# Interface.net
KiCad netlist of a schematic drawn in Altium Designer
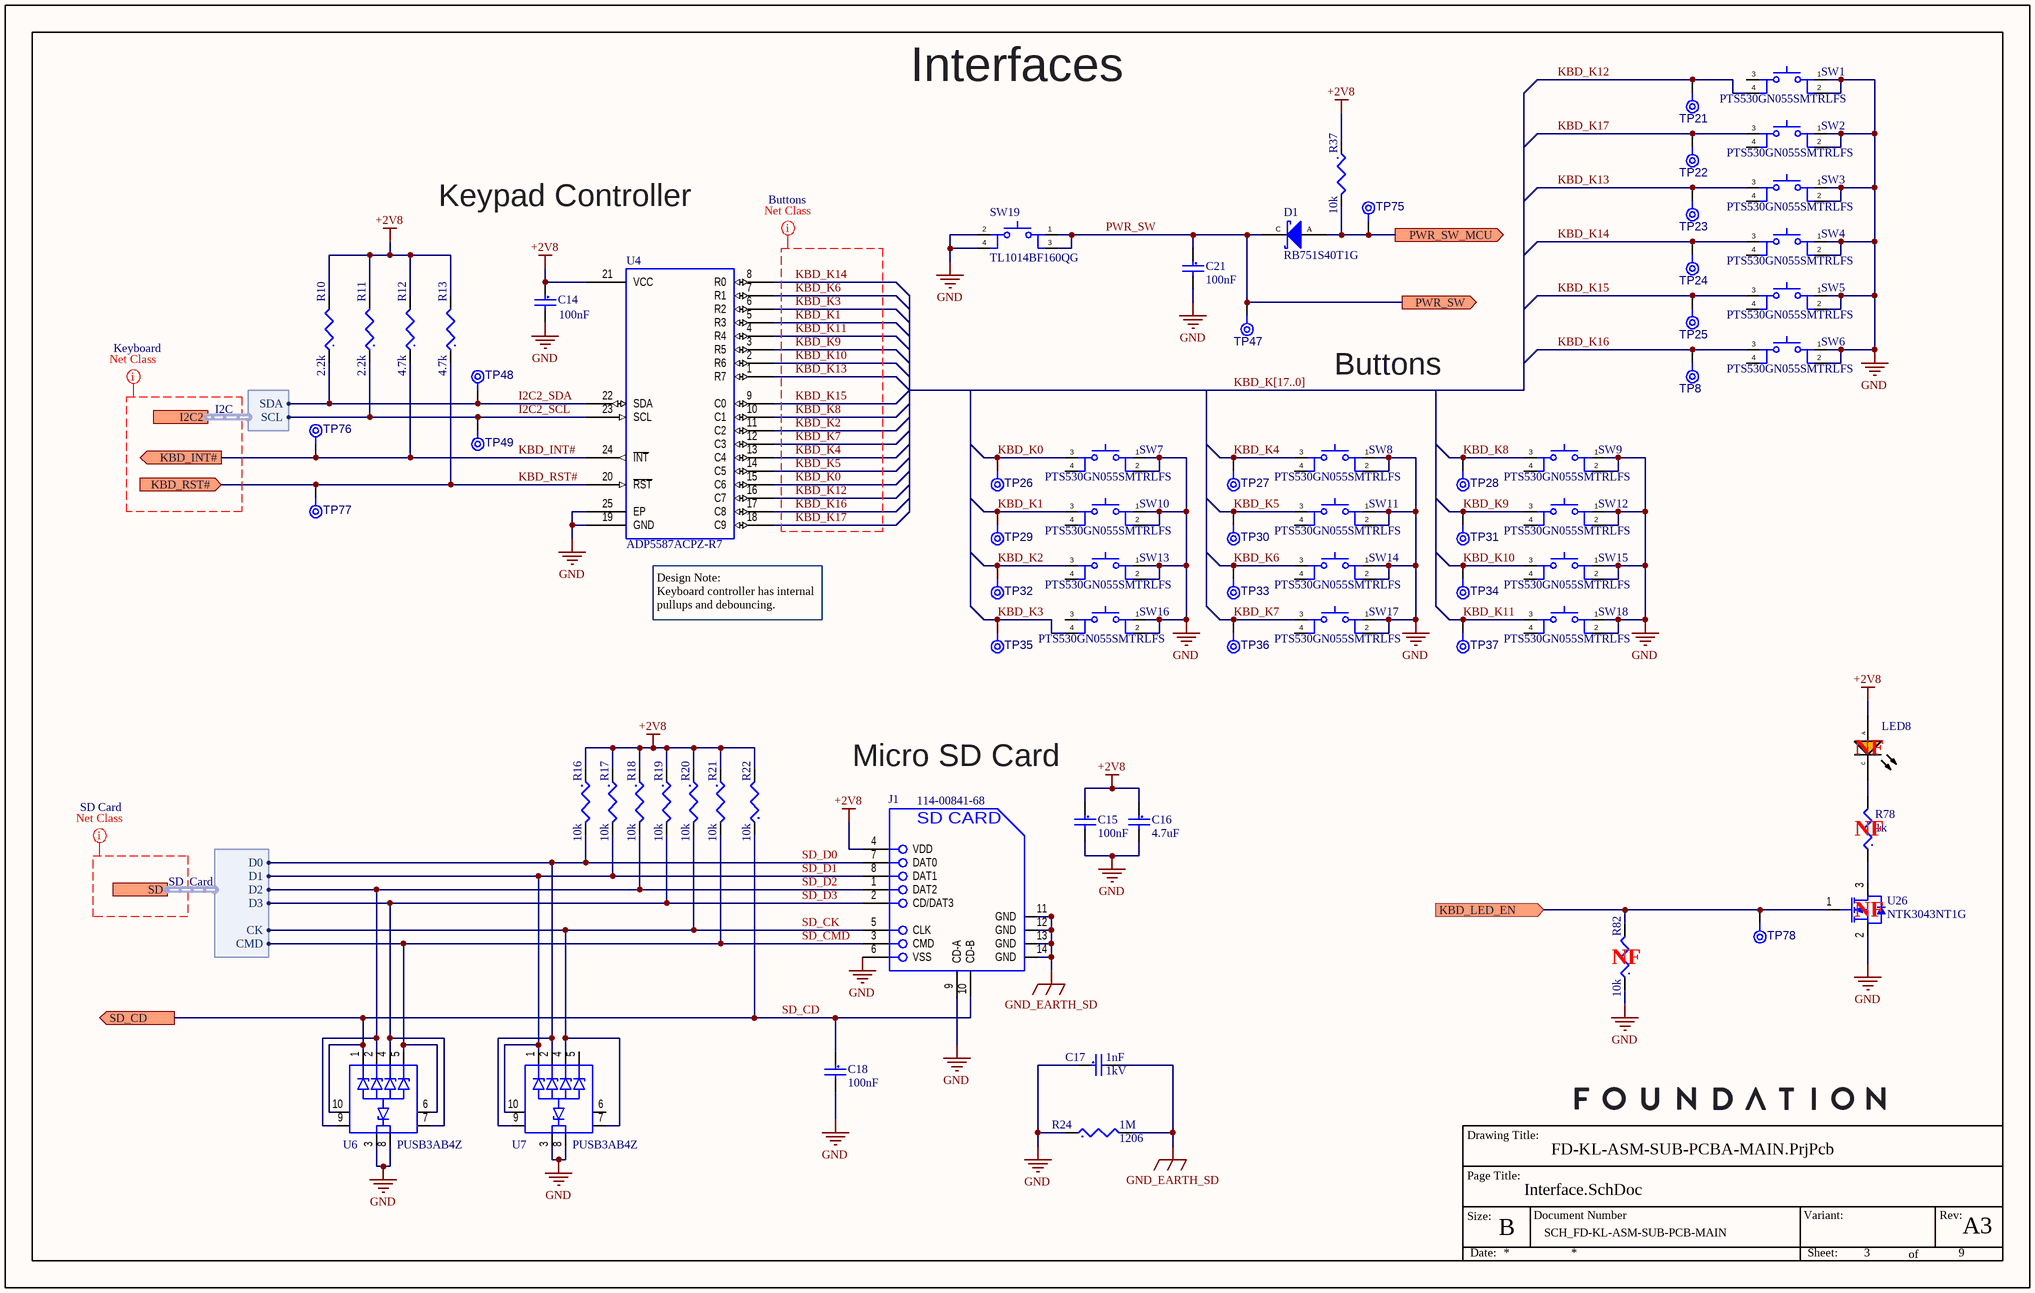
[diagram p0: Interface.SchDoc]

(export (version "E")
  (design (tool "Eeschema 10.0.6"))
  (components
    (comp (ref "C14")
      (value "CAP CER 0.1uF 16V 10% X7R 0402")
      (footprint "CAPC0402(1005)55_L")
      (description "0.1µF ±10% 16V Ceramic Capacitor X7R 0402 (1005 Metric)")
      (fields
        (field (name "CAPACITANCE") "100nF")
        (field (name "TOLERANCE") "10%")
        (field (name "VOLTAGE") "16V")
      )
      (libsource (lib "Altium Concord Pro on A365") (part "CAP-NP-2"))
    )
    (comp (ref "C15")
      (value "CAP CER 0.1uF 16V 10% X7R 0402")
      (footprint "CAPC0402(1005)55_L")
      (description "0.1µF ±10% 16V Ceramic Capacitor X7R 0402 (1005 Metric)")
      (fields
        (field (name "CAPACITANCE") "100nF")
        (field (name "TOLERANCE") "10%")
        (field (name "VOLTAGE") "16V")
      )
      (libsource (lib "Altium Concord Pro on A365") (part "CAP-NP-2"))
    )
    (comp (ref "C16")
      (value "CAP CER 4.7UF 10V 20% X5R 0402")
      (footprint "CAPC0402(1005)55_L")
      (description "4.7µF ±20% 10V Ceramic Capacitor X5R 0402 (1005 Metric)")
      (fields
        (field (name "CAPACITANCE") "4.7uF")
        (field (name "TOLERANCE") "20%")
        (field (name "VOLTAGE") "10V")
      )
      (libsource (lib "Altium Concord Pro on A365") (part "CAP-NP-2"))
    )
    (comp (ref "C17")
      (value "CAP CER 1000pF 1000V 10% X7R 0805")
      (footprint "CAPC0805(2012)145_N")
      (description "1000pF ±10% 1000V (1kV) Ceramic Capacitor X7R 0805 (2012 Metric)")
      (fields
        (field (name "CAPACITANCE") "1nF")
        (field (name "VOLTAGE RATING (DC)") "1kV")
        (field (name "TOLERANCE") "10%")
      )
      (libsource (lib "Altium Concord Pro on A365") (part "CAP-NP-2"))
    )
    (comp (ref "C18")
      (value "CAP CER 0.1uF 16V 10% X7R 0402")
      (footprint "CAPC0402(1005)55_L")
      (description "0.1µF ±10% 16V Ceramic Capacitor X7R 0402 (1005 Metric)")
      (fields
        (field (name "CAPACITANCE") "100nF")
        (field (name "TOLERANCE") "10%")
        (field (name "VOLTAGE") "16V")
      )
      (libsource (lib "Altium Concord Pro on A365") (part "CAP-NP-2"))
    )
    (comp (ref "C21")
      (value "CAP CER 0.1uF 16V 10% X7R 0402")
      (footprint "CAPC0402(1005)55_L")
      (description "0.1µF ±10% 16V Ceramic Capacitor X7R 0402 (1005 Metric)")
      (fields
        (field (name "CAPACITANCE") "100nF")
        (field (name "TOLERANCE") "10%")
        (field (name "VOLTAGE") "16V")
      )
      (libsource (lib "Altium Concord Pro on A365") (part "CAP-NP-2"))
    )
    (comp (ref "D1")
      (value "RB751S40T1G")
      (footprint "ON - SOD-523_V")
      (description "Diode Schottky 30V 30mA (DC) Surface Mount SOD-523")
      (libsource (lib "Altium Concord Pro on A365") (part "DSKY-AC-2"))
    )
    (comp (ref "J1")
      (value "114-00841-68")
      (footprint "AMPH - 114-00841-68_C-1")
      (description "10 (8 + 2) Position Card Connector Secure Digital - microSD™ Surface Mount, Right Angle Gold")
      (libsource (lib "Altium Concord Pro on A365") (part "CN-SD-1140084168"))
    )
    (comp (ref "LED8")
      (value "IN-S63AT5A")
      (footprint "LEDC0603(1608)65_L")
      (description "Amber 605nm LED Indication - Discrete 1.9V 0603 (1608 Metric)")
      (libsource (lib "Altium Concord Pro on A365") (part "LED-AMBER-AC-2"))
    )
    (comp (ref "R10")
      (value "RES 2.2K 1/16W 1% 0402")
      (footprint "RESC0402(1005)_L")
      (description "2.2 kOhms ±1% 0.063W, 1/16W Chip Resistor 0402 (1005 Metric)")
      (fields (field (name "RESISTANCE") "2.2k") (field (name "TOLERANCE") "1%"))
      (libsource (lib "Altium Concord Pro on A365") (part "RES-2"))
    )
    (comp (ref "R11")
      (value "RES 2.2K 1/16W 1% 0402")
      (footprint "RESC0402(1005)_L")
      (description "2.2 kOhms ±1% 0.063W, 1/16W Chip Resistor 0402 (1005 Metric)")
      (fields (field (name "RESISTANCE") "2.2k") (field (name "TOLERANCE") "1%"))
      (libsource (lib "Altium Concord Pro on A365") (part "RES-2"))
    )
    (comp (ref "R12")
      (value "RES 4.7K 1/16W 1% 0402")
      (footprint "RESC0402(1005)_L")
      (description "4.7 kOhms ±1% 0.063W, 1/16W Chip Resistor 0402 (1005 Metric) Automotive AEC-Q200 Thick Film")
      (fields (field (name "RESISTANCE") "4.7k") (field (name "TOLERANCE") "1%"))
      (libsource (lib "Altium Concord Pro on A365") (part "RES-2"))
    )
    (comp (ref "R13")
      (value "RES 4.7K 1/16W 1% 0402")
      (footprint "RESC0402(1005)_L")
      (description "4.7 kOhms ±1% 0.063W, 1/16W Chip Resistor 0402 (1005 Metric) Automotive AEC-Q200 Thick Film")
      (fields (field (name "RESISTANCE") "4.7k") (field (name "TOLERANCE") "1%"))
      (libsource (lib "Altium Concord Pro on A365") (part "RES-2"))
    )
    (comp (ref "R16")
      (value "RES 10K 1/16W 1% 0402")
      (footprint "RESC0402(1005)_L")
      (description "10 kOhms ±1% 0.063W, 1/16W Chip Resistor 0402 (1005 Metric)")
      (fields (field (name "RESISTANCE") "10k") (field (name "TOLERANCE") "1%"))
      (libsource (lib "Altium Concord Pro on A365") (part "RES-2"))
    )
    (comp (ref "R17")
      (value "RES 10K 1/16W 1% 0402")
      (footprint "RESC0402(1005)_L")
      (description "10 kOhms ±1% 0.063W, 1/16W Chip Resistor 0402 (1005 Metric)")
      (fields (field (name "RESISTANCE") "10k") (field (name "TOLERANCE") "1%"))
      (libsource (lib "Altium Concord Pro on A365") (part "RES-2"))
    )
    (comp (ref "R18")
      (value "RES 10K 1/16W 1% 0402")
      (footprint "RESC0402(1005)_L")
      (description "10 kOhms ±1% 0.063W, 1/16W Chip Resistor 0402 (1005 Metric)")
      (fields (field (name "RESISTANCE") "10k") (field (name "TOLERANCE") "1%"))
      (libsource (lib "Altium Concord Pro on A365") (part "RES-2"))
    )
    (comp (ref "R19")
      (value "RES 10K 1/16W 1% 0402")
      (footprint "RESC0402(1005)_L")
      (description "10 kOhms ±1% 0.063W, 1/16W Chip Resistor 0402 (1005 Metric)")
      (fields (field (name "RESISTANCE") "10k") (field (name "TOLERANCE") "1%"))
      (libsource (lib "Altium Concord Pro on A365") (part "RES-2"))
    )
    (comp (ref "R20")
      (value "RES 10K 1/16W 1% 0402")
      (footprint "RESC0402(1005)_L")
      (description "10 kOhms ±1% 0.063W, 1/16W Chip Resistor 0402 (1005 Metric)")
      (fields (field (name "RESISTANCE") "10k") (field (name "TOLERANCE") "1%"))
      (libsource (lib "Altium Concord Pro on A365") (part "RES-2"))
    )
    (comp (ref "R21")
      (value "RES 10K 1/16W 1% 0402")
      (footprint "RESC0402(1005)_L")
      (description "10 kOhms ±1% 0.063W, 1/16W Chip Resistor 0402 (1005 Metric)")
      (fields (field (name "RESISTANCE") "10k") (field (name "TOLERANCE") "1%"))
      (libsource (lib "Altium Concord Pro on A365") (part "RES-2"))
    )
    (comp (ref "R22")
      (value "RES 10K 1/16W 1% 0402")
      (footprint "RESC0402(1005)_L")
      (description "10 kOhms ±1% 0.063W, 1/16W Chip Resistor 0402 (1005 Metric)")
      (fields (field (name "RESISTANCE") "10k") (field (name "TOLERANCE") "1%"))
      (libsource (lib "Altium Concord Pro on A365") (part "RES-2"))
    )
    (comp (ref "R24")
      (value "RES 1.0M 1/4W 5% 1206")
      (footprint "RESC1206(3216)_L")
      (description "1 MOhms ±5% 0.25W, 1/4W Chip Resistor 1206 (3216 Metric) Moisture Resistant Thick Film")
      (fields
        (field (name "RESISTANCE") "1M")
        (field (name "TOLERANCE") "5%")
        (field (name "CASE CODE (IMPERIAL)") "1206")
      )
      (libsource (lib "Altium Concord Pro on A365") (part "RES-2"))
    )
    (comp (ref "R37")
      (value "RES 10K 1/16W 1% 0402")
      (footprint "RESC0402(1005)_L")
      (description "10 kOhms ±1% 0.063W, 1/16W Chip Resistor 0402 (1005 Metric)")
      (fields (field (name "RESISTANCE") "10k") (field (name "TOLERANCE") "1%"))
      (libsource (lib "Altium Concord Pro on A365") (part "RES-2"))
    )
    (comp (ref "R78")
      (value "RES 1.0K 1/16W 1% 0402")
      (footprint "RESC0402(1005)_L")
      (description "1 kOhms ±0.5% 0.063W, 1/16W Chip Resistor 0402 (1005 Metric) Automotive AEC-Q200 Thin Film")
      (fields (field (name "RESISTANCE") "1k") (field (name "TOLERANCE") "0.5%"))
      (libsource (lib "Altium Concord Pro on A365") (part "RES-2"))
    )
    (comp (ref "R82")
      (value "RES 10K 1/16W 1% 0402")
      (footprint "RESC0402(1005)_L")
      (description "10 kOhms ±1% 0.063W, 1/16W Chip Resistor 0402 (1005 Metric)")
      (fields (field (name "RESISTANCE") "10k") (field (name "TOLERANCE") "1%"))
      (libsource (lib "Altium Concord Pro on A365") (part "RES-2"))
    )
    (comp (ref "SW1")
      (value "PTS530GN055SMTRLFS")
      (footprint "C&K - PTS530_V")
      (description "Tactile Switch SPST-NO Top Actuated Surface Mount")
      (libsource (lib "Altium Concord Pro on A365") (part "TAC-4"))
    )
    (comp (ref "SW2")
      (value "PTS530GN055SMTRLFS")
      (footprint "C&K - PTS530_V")
      (description "Tactile Switch SPST-NO Top Actuated Surface Mount")
      (libsource (lib "Altium Concord Pro on A365") (part "TAC-4"))
    )
    (comp (ref "SW3")
      (value "PTS530GN055SMTRLFS")
      (footprint "C&K - PTS530_V")
      (description "Tactile Switch SPST-NO Top Actuated Surface Mount")
      (libsource (lib "Altium Concord Pro on A365") (part "TAC-4"))
    )
    (comp (ref "SW4")
      (value "PTS530GN055SMTRLFS")
      (footprint "C&K - PTS530_V")
      (description "Tactile Switch SPST-NO Top Actuated Surface Mount")
      (libsource (lib "Altium Concord Pro on A365") (part "TAC-4"))
    )
    (comp (ref "SW5")
      (value "PTS530GN055SMTRLFS")
      (footprint "C&K - PTS530_V")
      (description "Tactile Switch SPST-NO Top Actuated Surface Mount")
      (libsource (lib "Altium Concord Pro on A365") (part "TAC-4"))
    )
    (comp (ref "SW6")
      (value "PTS530GN055SMTRLFS")
      (footprint "C&K - PTS530_V")
      (description "Tactile Switch SPST-NO Top Actuated Surface Mount")
      (libsource (lib "Altium Concord Pro on A365") (part "TAC-4"))
    )
    (comp (ref "SW7")
      (value "PTS530GN055SMTRLFS")
      (footprint "C&K - PTS530_V")
      (description "Tactile Switch SPST-NO Top Actuated Surface Mount")
      (libsource (lib "Altium Concord Pro on A365") (part "TAC-4"))
    )
    (comp (ref "SW8")
      (value "PTS530GN055SMTRLFS")
      (footprint "C&K - PTS530_V")
      (description "Tactile Switch SPST-NO Top Actuated Surface Mount")
      (libsource (lib "Altium Concord Pro on A365") (part "TAC-4"))
    )
    (comp (ref "SW9")
      (value "PTS530GN055SMTRLFS")
      (footprint "C&K - PTS530_V")
      (description "Tactile Switch SPST-NO Top Actuated Surface Mount")
      (libsource (lib "Altium Concord Pro on A365") (part "TAC-4"))
    )
    (comp (ref "SW10")
      (value "PTS530GN055SMTRLFS")
      (footprint "C&K - PTS530_V")
      (description "Tactile Switch SPST-NO Top Actuated Surface Mount")
      (libsource (lib "Altium Concord Pro on A365") (part "TAC-4"))
    )
    (comp (ref "SW11")
      (value "PTS530GN055SMTRLFS")
      (footprint "C&K - PTS530_V")
      (description "Tactile Switch SPST-NO Top Actuated Surface Mount")
      (libsource (lib "Altium Concord Pro on A365") (part "TAC-4"))
    )
    (comp (ref "SW12")
      (value "PTS530GN055SMTRLFS")
      (footprint "C&K - PTS530_V")
      (description "Tactile Switch SPST-NO Top Actuated Surface Mount")
      (libsource (lib "Altium Concord Pro on A365") (part "TAC-4"))
    )
    (comp (ref "SW13")
      (value "PTS530GN055SMTRLFS")
      (footprint "C&K - PTS530_V")
      (description "Tactile Switch SPST-NO Top Actuated Surface Mount")
      (libsource (lib "Altium Concord Pro on A365") (part "TAC-4"))
    )
    (comp (ref "SW14")
      (value "PTS530GN055SMTRLFS")
      (footprint "C&K - PTS530_V")
      (description "Tactile Switch SPST-NO Top Actuated Surface Mount")
      (libsource (lib "Altium Concord Pro on A365") (part "TAC-4"))
    )
    (comp (ref "SW15")
      (value "PTS530GN055SMTRLFS")
      (footprint "C&K - PTS530_V")
      (description "Tactile Switch SPST-NO Top Actuated Surface Mount")
      (libsource (lib "Altium Concord Pro on A365") (part "TAC-4"))
    )
    (comp (ref "SW16")
      (value "PTS530GN055SMTRLFS")
      (footprint "C&K - PTS530_V")
      (description "Tactile Switch SPST-NO Top Actuated Surface Mount")
      (libsource (lib "Altium Concord Pro on A365") (part "TAC-4"))
    )
    (comp (ref "SW17")
      (value "PTS530GN055SMTRLFS")
      (footprint "C&K - PTS530_V")
      (description "Tactile Switch SPST-NO Top Actuated Surface Mount")
      (libsource (lib "Altium Concord Pro on A365") (part "TAC-4"))
    )
    (comp (ref "SW18")
      (value "PTS530GN055SMTRLFS")
      (footprint "C&K - PTS530_V")
      (description "Tactile Switch SPST-NO Top Actuated Surface Mount")
      (libsource (lib "Altium Concord Pro on A365") (part "TAC-4"))
    )
    (comp (ref "SW19")
      (value "TL1014BF160QG")
      (footprint "E-SWITCH - TL1014BFXXXQG")
      (description "Tactile Switch SPST-NO Side Actuated Surface Mount, Right Angle")
      (libsource (lib "Altium Concord Pro on A365") (part "TAC-4-13"))
    )
    (comp (ref "TP8")
      (value "TPAD8R")
      (footprint "TP08R")
      (description "0.8mm round")
      (libsource (lib "Altium Concord Pro on A365") (part "TP-R-1"))
    )
    (comp (ref "TP21")
      (value "TPAD8R")
      (footprint "TP08R")
      (description "0.8mm round")
      (libsource (lib "Altium Concord Pro on A365") (part "TP-R-1"))
    )
    (comp (ref "TP22")
      (value "TPAD8R")
      (footprint "TP08R")
      (description "0.8mm round")
      (libsource (lib "Altium Concord Pro on A365") (part "TP-R-1"))
    )
    (comp (ref "TP23")
      (value "TPAD8R")
      (footprint "TP08R")
      (description "0.8mm round")
      (libsource (lib "Altium Concord Pro on A365") (part "TP-R-1"))
    )
    (comp (ref "TP24")
      (value "TPAD8R")
      (footprint "TP08R")
      (description "0.8mm round")
      (libsource (lib "Altium Concord Pro on A365") (part "TP-R-1"))
    )
    (comp (ref "TP25")
      (value "TPAD8R")
      (footprint "TP08R")
      (description "0.8mm round")
      (libsource (lib "Altium Concord Pro on A365") (part "TP-R-1"))
    )
    (comp (ref "TP26")
      (value "TPAD8R")
      (footprint "TP08R")
      (description "0.8mm round")
      (libsource (lib "Altium Concord Pro on A365") (part "TP-R-1"))
    )
    (comp (ref "TP27")
      (value "TPAD8R")
      (footprint "TP08R")
      (description "0.8mm round")
      (libsource (lib "Altium Concord Pro on A365") (part "TP-R-1"))
    )
    (comp (ref "TP28")
      (value "TPAD8R")
      (footprint "TP08R")
      (description "0.8mm round")
      (libsource (lib "Altium Concord Pro on A365") (part "TP-R-1"))
    )
    (comp (ref "TP29")
      (value "TPAD8R")
      (footprint "TP08R")
      (description "0.8mm round")
      (libsource (lib "Altium Concord Pro on A365") (part "TP-R-1"))
    )
    (comp (ref "TP30")
      (value "TPAD8R")
      (footprint "TP08R")
      (description "0.8mm round")
      (libsource (lib "Altium Concord Pro on A365") (part "TP-R-1"))
    )
    (comp (ref "TP31")
      (value "TPAD8R")
      (footprint "TP08R")
      (description "0.8mm round")
      (libsource (lib "Altium Concord Pro on A365") (part "TP-R-1"))
    )
    (comp (ref "TP32")
      (value "TPAD8R")
      (footprint "TP08R")
      (description "0.8mm round")
      (libsource (lib "Altium Concord Pro on A365") (part "TP-R-1"))
    )
    (comp (ref "TP33")
      (value "TPAD8R")
      (footprint "TP08R")
      (description "0.8mm round")
      (libsource (lib "Altium Concord Pro on A365") (part "TP-R-1"))
    )
    (comp (ref "TP34")
      (value "TPAD8R")
      (footprint "TP08R")
      (description "0.8mm round")
      (libsource (lib "Altium Concord Pro on A365") (part "TP-R-1"))
    )
    (comp (ref "TP35")
      (value "TPAD8R")
      (footprint "TP08R")
      (description "0.8mm round")
      (libsource (lib "Altium Concord Pro on A365") (part "TP-R-1"))
    )
    (comp (ref "TP36")
      (value "TPAD8R")
      (footprint "TP08R")
      (description "0.8mm round")
      (libsource (lib "Altium Concord Pro on A365") (part "TP-R-1"))
    )
    (comp (ref "TP37")
      (value "TPAD8R")
      (footprint "TP08R")
      (description "0.8mm round")
      (libsource (lib "Altium Concord Pro on A365") (part "TP-R-1"))
    )
    (comp (ref "TP47")
      (value "TPAD8R")
      (footprint "TP08R")
      (description "0.8mm round")
      (libsource (lib "Altium Concord Pro on A365") (part "TP-R-1"))
    )
    (comp (ref "TP48")
      (value "TPAD8R")
      (footprint "TP08R")
      (description "0.8mm round")
      (libsource (lib "Altium Concord Pro on A365") (part "TP-R-1"))
    )
    (comp (ref "TP49")
      (value "TPAD8R")
      (footprint "TP08R")
      (description "0.8mm round")
      (libsource (lib "Altium Concord Pro on A365") (part "TP-R-1"))
    )
    (comp (ref "TP75")
      (value "TPAD8R")
      (footprint "TP08R")
      (description "0.8mm round")
      (libsource (lib "Altium Concord Pro on A365") (part "TP-R-1"))
    )
    (comp (ref "TP76")
      (value "TPAD8R")
      (footprint "TP08R")
      (description "0.8mm round")
      (libsource (lib "Altium Concord Pro on A365") (part "TP-R-1"))
    )
    (comp (ref "TP77")
      (value "TPAD8R")
      (footprint "TP08R")
      (description "0.8mm round")
      (libsource (lib "Altium Concord Pro on A365") (part "TP-R-1"))
    )
    (comp (ref "TP78")
      (value "TPAD8R")
      (footprint "TP08R")
      (description "0.8mm round")
      (libsource (lib "Altium Concord Pro on A365") (part "TP-R-1"))
    )
    (comp (ref "U4")
      (value "ADP5587ACPZ-R7")
      (footprint "ADEV - LFCSP-24_L")
      (description "I/O Expander 18 I²C 400kHz 24-LFCSP-WQ (4x4)")
      (libsource (lib "Altium Concord Pro on A365") (part "ADP5587ACPZ"))
    )
    (comp (ref "U6")
      (value "PUSB3AB4Z")
      (footprint "NEXP - DFN2510A-10_L")
      (description "TVS DIODE 3.3V 5V DFN2510A-10")
      (libsource (lib "Altium Concord Pro on A365") (part "DTVS-ARY-4-1245-8-10"))
    )
    (comp (ref "U7")
      (value "PUSB3AB4Z")
      (footprint "NEXP - DFN2510A-10_L")
      (description "TVS DIODE 3.3V 5V DFN2510A-10")
      (libsource (lib "Altium Concord Pro on A365") (part "DTVS-ARY-4-1245-8-10"))
    )
    (comp (ref "U26")
      (value "NTK3043NT1G")
      (footprint "SOT-723-3(40)_N")
      (description "N-Channel 20V 210mA (Ta) 310mW (Ta) Surface Mount SOT-723")
      (libsource (lib "Altium Concord Pro on A365") (part "NMOS-GSD-3"))
    )
  )
  (nets
    (net (code "3") (name "+2V8") (class "Default")
      (node (ref "C14") (pin "1") (pinfunction "1_1") (pintype "passive"))
      (node (ref "C15") (pin "1") (pinfunction "1_1") (pintype "passive"))
      (node (ref "C16") (pin "1") (pinfunction "1_1") (pintype "passive"))
      (node (ref "J1") (pin "4") (pinfunction "VDD_4") (pintype "passive"))
      (node (ref "LED8") (pin "A") (pinfunction "A_A") (pintype "passive"))
      (node (ref "R10") (pin "2") (pinfunction "2_2") (pintype "passive"))
      (node (ref "R11") (pin "2") (pinfunction "2_2") (pintype "passive"))
      (node (ref "R12") (pin "2") (pinfunction "2_2") (pintype "passive"))
      (node (ref "R13") (pin "2") (pinfunction "2_2") (pintype "passive"))
      (node (ref "R16") (pin "1") (pinfunction "1_1") (pintype "passive"))
      (node (ref "R17") (pin "1") (pinfunction "1_1") (pintype "passive"))
      (node (ref "R18") (pin "1") (pinfunction "1_1") (pintype "passive"))
      (node (ref "R19") (pin "1") (pinfunction "1_1") (pintype "passive"))
      (node (ref "R20") (pin "1") (pinfunction "1_1") (pintype "passive"))
      (node (ref "R21") (pin "1") (pinfunction "1_1") (pintype "passive"))
      (node (ref "R22") (pin "2") (pinfunction "2_2") (pintype "passive"))
      (node (ref "R37") (pin "1") (pinfunction "1_1") (pintype "passive"))
      (node (ref "U4") (pin "21") (pinfunction "VCC_21") (pintype "power_in"))
    )
    (net (code "4") (name "/I2C2_SCL") (class "Default")
      (node (ref "R11") (pin "1") (pinfunction "1_1") (pintype "passive"))
      (node (ref "TP49") (pin "1") (pinfunction "TP_1") (pintype "passive"))
      (node (ref "U4") (pin "23") (pinfunction "SCL_23") (pintype "input"))
    )
    (net (code "5") (name "/I2C2_SDA") (class "Default")
      (node (ref "R10") (pin "1") (pinfunction "1_1") (pintype "passive"))
      (node (ref "TP48") (pin "1") (pinfunction "TP_1") (pintype "passive"))
      (node (ref "U4") (pin "22") (pinfunction "SDA_22") (pintype "bidirectional"))
    )
    (net (code "6") (name "/KBD_INT#") (class "Default")
      (node (ref "R12") (pin "1") (pinfunction "1_1") (pintype "passive"))
      (node (ref "TP76") (pin "1") (pinfunction "TP_1") (pintype "passive"))
      (node (ref "U4") (pin "24") (pinfunction "~{INT}_24") (pintype "output"))
    )
    (net (code "7") (name "/KBD_K0") (class "Default")
      (node (ref "SW7") (pin "3") (pinfunction "3_3") (pintype "passive"))
      (node (ref "TP26") (pin "1") (pinfunction "TP_1") (pintype "passive"))
      (node (ref "U4") (pin "15") (pinfunction "C6_15") (pintype "bidirectional"))
    )
    (net (code "8") (name "/KBD_K1") (class "Default")
      (node (ref "SW10") (pin "3") (pinfunction "3_3") (pintype "passive"))
      (node (ref "TP29") (pin "1") (pinfunction "TP_1") (pintype "passive"))
      (node (ref "U4") (pin "5") (pinfunction "R3_5") (pintype "bidirectional"))
    )
    (net (code "9") (name "/KBD_K2") (class "Default")
      (node (ref "SW13") (pin "3") (pinfunction "3_3") (pintype "passive"))
      (node (ref "TP32") (pin "1") (pinfunction "TP_1") (pintype "passive"))
      (node (ref "U4") (pin "11") (pinfunction "C2_11") (pintype "bidirectional"))
    )
    (net (code "10") (name "/KBD_K3") (class "Default")
      (node (ref "SW16") (pin "4") (pinfunction "4_4") (pintype "passive"))
      (node (ref "TP35") (pin "1") (pinfunction "TP_1") (pintype "passive"))
      (node (ref "U4") (pin "6") (pinfunction "R2_6") (pintype "bidirectional"))
    )
    (net (code "11") (name "/KBD_K4") (class "Default")
      (node (ref "SW8") (pin "3") (pinfunction "3_3") (pintype "passive"))
      (node (ref "TP27") (pin "1") (pinfunction "TP_1") (pintype "passive"))
      (node (ref "U4") (pin "13") (pinfunction "C4_13") (pintype "bidirectional"))
    )
    (net (code "12") (name "/KBD_K5") (class "Default")
      (node (ref "SW11") (pin "3") (pinfunction "3_3") (pintype "passive"))
      (node (ref "TP30") (pin "1") (pinfunction "TP_1") (pintype "passive"))
      (node (ref "U4") (pin "14") (pinfunction "C5_14") (pintype "bidirectional"))
    )
    (net (code "13") (name "/KBD_K6") (class "Default")
      (node (ref "SW14") (pin "3") (pinfunction "3_3") (pintype "passive"))
      (node (ref "TP33") (pin "1") (pinfunction "TP_1") (pintype "passive"))
      (node (ref "U4") (pin "7") (pinfunction "R1_7") (pintype "bidirectional"))
    )
    (net (code "14") (name "/KBD_K7") (class "Default")
      (node (ref "SW17") (pin "3") (pinfunction "3_3") (pintype "passive"))
      (node (ref "TP36") (pin "1") (pinfunction "TP_1") (pintype "passive"))
      (node (ref "U4") (pin "12") (pinfunction "C3_12") (pintype "bidirectional"))
    )
    (net (code "15") (name "/KBD_K8") (class "Default")
      (node (ref "SW9") (pin "3") (pinfunction "3_3") (pintype "passive"))
      (node (ref "TP28") (pin "1") (pinfunction "TP_1") (pintype "passive"))
      (node (ref "U4") (pin "10") (pinfunction "C1_10") (pintype "bidirectional"))
    )
    (net (code "16") (name "/KBD_K9") (class "Default")
      (node (ref "SW12") (pin "3") (pinfunction "3_3") (pintype "passive"))
      (node (ref "TP31") (pin "1") (pinfunction "TP_1") (pintype "passive"))
      (node (ref "U4") (pin "3") (pinfunction "R5_3") (pintype "bidirectional"))
    )
    (net (code "17") (name "/KBD_K10") (class "Default")
      (node (ref "SW15") (pin "3") (pinfunction "3_3") (pintype "passive"))
      (node (ref "TP34") (pin "1") (pinfunction "TP_1") (pintype "passive"))
      (node (ref "U4") (pin "2") (pinfunction "R6_2") (pintype "bidirectional"))
    )
    (net (code "18") (name "/KBD_K11") (class "Default")
      (node (ref "SW18") (pin "3") (pinfunction "3_3") (pintype "passive"))
      (node (ref "TP37") (pin "1") (pinfunction "TP_1") (pintype "passive"))
      (node (ref "U4") (pin "4") (pinfunction "R4_4") (pintype "bidirectional"))
    )
    (net (code "19") (name "/KBD_K12") (class "Default")
      (node (ref "SW1") (pin "4") (pinfunction "4_4") (pintype "passive"))
      (node (ref "TP21") (pin "1") (pinfunction "TP_1") (pintype "passive"))
      (node (ref "U4") (pin "16") (pinfunction "C7_16") (pintype "bidirectional"))
    )
    (net (code "20") (name "/KBD_K13") (class "Default")
      (node (ref "SW3") (pin "3") (pinfunction "3_3") (pintype "passive"))
      (node (ref "TP23") (pin "1") (pinfunction "TP_1") (pintype "passive"))
      (node (ref "U4") (pin "1") (pinfunction "R7_1") (pintype "bidirectional"))
    )
    (net (code "21") (name "/KBD_K14") (class "Default")
      (node (ref "SW4") (pin "3") (pinfunction "3_3") (pintype "passive"))
      (node (ref "TP24") (pin "1") (pinfunction "TP_1") (pintype "passive"))
      (node (ref "U4") (pin "8") (pinfunction "R0_8") (pintype "bidirectional"))
    )
    (net (code "22") (name "/KBD_K15") (class "Default")
      (node (ref "SW5") (pin "3") (pinfunction "3_3") (pintype "passive"))
      (node (ref "TP25") (pin "1") (pinfunction "TP_1") (pintype "passive"))
      (node (ref "U4") (pin "9") (pinfunction "C0_9") (pintype "bidirectional"))
    )
    (net (code "23") (name "/KBD_K16") (class "Default")
      (node (ref "SW6") (pin "3") (pinfunction "3_3") (pintype "passive"))
      (node (ref "TP8") (pin "1") (pinfunction "TP_1") (pintype "passive"))
      (node (ref "U4") (pin "17") (pinfunction "C8_17") (pintype "bidirectional"))
    )
    (net (code "24") (name "/KBD_K17") (class "Default")
      (node (ref "SW2") (pin "3") (pinfunction "3_3") (pintype "passive"))
      (node (ref "TP22") (pin "1") (pinfunction "TP_1") (pintype "passive"))
      (node (ref "U4") (pin "18") (pinfunction "C9_18") (pintype "bidirectional"))
    )
    (net (code "26") (name "/KBD_LED_EN") (class "Default")
      (node (ref "R82") (pin "2") (pinfunction "2_2") (pintype "passive"))
      (node (ref "TP78") (pin "1") (pinfunction "TP_1") (pintype "passive"))
      (node (ref "U26") (pin "1") (pinfunction "G_1") (pintype "passive"))
    )
    (net (code "27") (name "/KBD_RST#") (class "Default")
      (node (ref "R13") (pin "1") (pinfunction "1_1") (pintype "passive"))
      (node (ref "TP77") (pin "1") (pinfunction "TP_1") (pintype "passive"))
      (node (ref "U4") (pin "20") (pinfunction "~{RST}_20") (pintype "input"))
    )
    (net (code "28") (name "/PWR_SW") (class "Default")
      (node (ref "C21") (pin "1") (pinfunction "1_1") (pintype "passive"))
      (node (ref "D1") (pin "C") (pinfunction "C_C") (pintype "passive"))
      (node (ref "SW19") (pin "1") (pinfunction "1_1") (pintype "passive"))
      (node (ref "SW19") (pin "3") (pinfunction "3_3") (pintype "passive"))
      (node (ref "TP47") (pin "1") (pinfunction "TP_1") (pintype "passive"))
    )
    (net (code "29") (name "/PWR_SW_MCU") (class "Default")
      (node (ref "D1") (pin "A") (pinfunction "A_A") (pintype "passive"))
      (node (ref "R37") (pin "2") (pinfunction "2_2") (pintype "passive"))
      (node (ref "TP75") (pin "1") (pinfunction "TP_1") (pintype "passive"))
    )
    (net (code "30") (name "/SD_CD") (class "Default")
      (node (ref "C18") (pin "1") (pinfunction "1_1") (pintype "passive"))
      (node (ref "J1") (pin "10") (pinfunction "CD-B_10") (pintype "passive"))
      (node (ref "R22") (pin "1") (pinfunction "1_1") (pintype "passive"))
      (node (ref "U6") (pin "1") (pinfunction "DIODE_1") (pintype "passive"))
      (node (ref "U6") (pin "10") (pinfunction "DIODE_10") (pintype "passive"))
    )
    (net (code "31") (name "/SD_CK") (class "Default")
      (node (ref "J1") (pin "5") (pinfunction "CLK_5") (pintype "passive"))
      (node (ref "R20") (pin "2") (pinfunction "2_2") (pintype "passive"))
      (node (ref "U7") (pin "4") (pinfunction "DIODE_4") (pintype "passive"))
      (node (ref "U7") (pin "7") (pinfunction "DIODE_7") (pintype "passive"))
    )
    (net (code "32") (name "/SD_CMD") (class "Default")
      (node (ref "J1") (pin "3") (pinfunction "CMD_3") (pintype "passive"))
      (node (ref "R21") (pin "2") (pinfunction "2_2") (pintype "passive"))
      (node (ref "U6") (pin "5") (pinfunction "DIODE_5") (pintype "passive"))
      (node (ref "U6") (pin "6") (pinfunction "DIODE_6") (pintype "passive"))
    )
    (net (code "33") (name "/SD_D0") (class "Default")
      (node (ref "J1") (pin "7") (pinfunction "DAT0_7") (pintype "passive"))
      (node (ref "R16") (pin "2") (pinfunction "2_2") (pintype "passive"))
      (node (ref "U7") (pin "2") (pinfunction "A_2") (pintype "passive"))
      (node (ref "U7") (pin "9") (pinfunction "DIODE_9") (pintype "passive"))
    )
    (net (code "34") (name "/SD_D1") (class "Default")
      (node (ref "J1") (pin "8") (pinfunction "DAT1_8") (pintype "passive"))
      (node (ref "R17") (pin "2") (pinfunction "2_2") (pintype "passive"))
      (node (ref "U7") (pin "1") (pinfunction "DIODE_1") (pintype "passive"))
      (node (ref "U7") (pin "10") (pinfunction "DIODE_10") (pintype "passive"))
    )
    (net (code "35") (name "/SD_D2") (class "Default")
      (node (ref "J1") (pin "1") (pinfunction "DAT2_1") (pintype "passive"))
      (node (ref "R18") (pin "2") (pinfunction "2_2") (pintype "passive"))
      (node (ref "U6") (pin "2") (pinfunction "A_2") (pintype "passive"))
      (node (ref "U6") (pin "9") (pinfunction "DIODE_9") (pintype "passive"))
    )
    (net (code "36") (name "/SD_D3") (class "Default")
      (node (ref "J1") (pin "2") (pinfunction "CD/DAT3_2") (pintype "passive"))
      (node (ref "R19") (pin "2") (pinfunction "2_2") (pintype "passive"))
      (node (ref "U6") (pin "4") (pinfunction "DIODE_4") (pintype "passive"))
      (node (ref "U6") (pin "7") (pinfunction "DIODE_7") (pintype "passive"))
    )
    (net (code "39") (name "GND") (class "Default")
      (node (ref "C14") (pin "2") (pinfunction "2_2") (pintype "passive"))
      (node (ref "C15") (pin "2") (pinfunction "2_2") (pintype "passive"))
      (node (ref "C16") (pin "2") (pinfunction "2_2") (pintype "passive"))
      (node (ref "C17") (pin "1") (pinfunction "1_1") (pintype "passive"))
      (node (ref "C18") (pin "2") (pinfunction "2_2") (pintype "passive"))
      (node (ref "C21") (pin "2") (pinfunction "2_2") (pintype "passive"))
      (node (ref "J1") (pin "6") (pinfunction "VSS_6") (pintype "passive"))
      (node (ref "J1") (pin "9") (pinfunction "CD-A_9") (pintype "passive"))
      (node (ref "R24") (pin "1") (pinfunction "1_1") (pintype "passive"))
      (node (ref "R82") (pin "1") (pinfunction "1_1") (pintype "passive"))
      (node (ref "SW1") (pin "1") (pinfunction "1_1") (pintype "passive"))
      (node (ref "SW1") (pin "2") (pinfunction "2_2") (pintype "passive"))
      (node (ref "SW10") (pin "1") (pinfunction "1_1") (pintype "passive"))
      (node (ref "SW10") (pin "2") (pinfunction "2_2") (pintype "passive"))
      (node (ref "SW11") (pin "1") (pinfunction "1_1") (pintype "passive"))
      (node (ref "SW11") (pin "2") (pinfunction "2_2") (pintype "passive"))
      (node (ref "SW12") (pin "1") (pinfunction "1_1") (pintype "passive"))
      (node (ref "SW12") (pin "2") (pinfunction "2_2") (pintype "passive"))
      (node (ref "SW13") (pin "1") (pinfunction "1_1") (pintype "passive"))
      (node (ref "SW13") (pin "2") (pinfunction "2_2") (pintype "passive"))
      (node (ref "SW14") (pin "1") (pinfunction "1_1") (pintype "passive"))
      (node (ref "SW14") (pin "2") (pinfunction "2_2") (pintype "passive"))
      (node (ref "SW15") (pin "1") (pinfunction "1_1") (pintype "passive"))
      (node (ref "SW15") (pin "2") (pinfunction "2_2") (pintype "passive"))
      (node (ref "SW16") (pin "1") (pinfunction "1_1") (pintype "passive"))
      (node (ref "SW16") (pin "2") (pinfunction "2_2") (pintype "passive"))
      (node (ref "SW17") (pin "1") (pinfunction "1_1") (pintype "passive"))
      (node (ref "SW17") (pin "2") (pinfunction "2_2") (pintype "passive"))
      (node (ref "SW18") (pin "1") (pinfunction "1_1") (pintype "passive"))
      (node (ref "SW18") (pin "2") (pinfunction "2_2") (pintype "passive"))
      (node (ref "SW19") (pin "2") (pinfunction "2_2") (pintype "passive"))
      (node (ref "SW19") (pin "4") (pinfunction "4_4") (pintype "passive"))
      (node (ref "SW2") (pin "1") (pinfunction "1_1") (pintype "passive"))
      (node (ref "SW2") (pin "2") (pinfunction "2_2") (pintype "passive"))
      (node (ref "SW3") (pin "1") (pinfunction "1_1") (pintype "passive"))
      (node (ref "SW3") (pin "2") (pinfunction "2_2") (pintype "passive"))
      (node (ref "SW4") (pin "1") (pinfunction "1_1") (pintype "passive"))
      (node (ref "SW4") (pin "2") (pinfunction "2_2") (pintype "passive"))
      (node (ref "SW5") (pin "1") (pinfunction "1_1") (pintype "passive"))
      (node (ref "SW5") (pin "2") (pinfunction "2_2") (pintype "passive"))
      (node (ref "SW6") (pin "1") (pinfunction "1_1") (pintype "passive"))
      (node (ref "SW6") (pin "2") (pinfunction "2_2") (pintype "passive"))
      (node (ref "SW7") (pin "1") (pinfunction "1_1") (pintype "passive"))
      (node (ref "SW7") (pin "2") (pinfunction "2_2") (pintype "passive"))
      (node (ref "SW8") (pin "1") (pinfunction "1_1") (pintype "passive"))
      (node (ref "SW8") (pin "2") (pinfunction "2_2") (pintype "passive"))
      (node (ref "SW9") (pin "1") (pinfunction "1_1") (pintype "passive"))
      (node (ref "SW9") (pin "2") (pinfunction "2_2") (pintype "passive"))
      (node (ref "U26") (pin "2") (pinfunction "S_2") (pintype "passive"))
      (node (ref "U4") (pin "19") (pinfunction "GND_19") (pintype "power_in"))
      (node (ref "U4") (pin "25") (pinfunction "EP_25") (pintype "power_in"))
      (node (ref "U6") (pin "3") (pinfunction "DIODE_3") (pintype "passive"))
      (node (ref "U6") (pin "8") (pinfunction "DIODE_8") (pintype "passive"))
      (node (ref "U7") (pin "3") (pinfunction "DIODE_3") (pintype "passive"))
      (node (ref "U7") (pin "8") (pinfunction "DIODE_8") (pintype "passive"))
    )
    (net (code "40") (name "GND_EARTH_SD") (class "Default")
      (node (ref "C17") (pin "2") (pinfunction "2_2") (pintype "passive"))
      (node (ref "J1") (pin "11") (pinfunction "GND_11") (pintype "passive"))
      (node (ref "J1") (pin "12") (pinfunction "GND_12") (pintype "passive"))
      (node (ref "J1") (pin "13") (pinfunction "GND_13") (pintype "passive"))
      (node (ref "J1") (pin "14") (pinfunction "GND_14") (pintype "passive"))
      (node (ref "R24") (pin "2") (pinfunction "2_2") (pintype "passive"))
    )
    (net (code "41") (name "Net-(LED8-PadC)") (class "Default")
      (node (ref "LED8") (pin "C") (pinfunction "C_C") (pintype "passive"))
      (node (ref "R78") (pin "2") (pinfunction "2_2") (pintype "passive"))
    )
    (net (code "42") (name "Net-(U26-D)") (class "Default")
      (node (ref "R78") (pin "1") (pinfunction "1_1") (pintype "passive"))
      (node (ref "U26") (pin "3") (pinfunction "D_3") (pintype "passive"))
    )
    (net (code "43") (name "unconnected-(SW1-Pad3)") (class "Default")
      (node (ref "SW1") (pin "3") (pinfunction "3_3") (pintype "passive"))
    )
    (net (code "44") (name "unconnected-(SW2-Pad4)") (class "Default")
      (node (ref "SW2") (pin "4") (pinfunction "4_4") (pintype "passive"))
    )
    (net (code "45") (name "unconnected-(SW3-Pad4)") (class "Default")
      (node (ref "SW3") (pin "4") (pinfunction "4_4") (pintype "passive"))
    )
    (net (code "46") (name "unconnected-(SW4-Pad4)") (class "Default")
      (node (ref "SW4") (pin "4") (pinfunction "4_4") (pintype "passive"))
    )
    (net (code "47") (name "unconnected-(SW5-Pad4)") (class "Default")
      (node (ref "SW5") (pin "4") (pinfunction "4_4") (pintype "passive"))
    )
    (net (code "48") (name "unconnected-(SW6-Pad4)") (class "Default")
      (node (ref "SW6") (pin "4") (pinfunction "4_4") (pintype "passive"))
    )
    (net (code "49") (name "unconnected-(SW7-Pad4)") (class "Default")
      (node (ref "SW7") (pin "4") (pinfunction "4_4") (pintype "passive"))
    )
    (net (code "50") (name "unconnected-(SW8-Pad4)") (class "Default")
      (node (ref "SW8") (pin "4") (pinfunction "4_4") (pintype "passive"))
    )
    (net (code "51") (name "unconnected-(SW9-Pad4)") (class "Default")
      (node (ref "SW9") (pin "4") (pinfunction "4_4") (pintype "passive"))
    )
    (net (code "52") (name "unconnected-(SW10-Pad4)") (class "Default")
      (node (ref "SW10") (pin "4") (pinfunction "4_4") (pintype "passive"))
    )
    (net (code "53") (name "unconnected-(SW11-Pad4)") (class "Default")
      (node (ref "SW11") (pin "4") (pinfunction "4_4") (pintype "passive"))
    )
    (net (code "54") (name "unconnected-(SW12-Pad4)") (class "Default")
      (node (ref "SW12") (pin "4") (pinfunction "4_4") (pintype "passive"))
    )
    (net (code "55") (name "unconnected-(SW13-Pad4)") (class "Default")
      (node (ref "SW13") (pin "4") (pinfunction "4_4") (pintype "passive"))
    )
    (net (code "56") (name "unconnected-(SW14-Pad4)") (class "Default")
      (node (ref "SW14") (pin "4") (pinfunction "4_4") (pintype "passive"))
    )
    (net (code "57") (name "unconnected-(SW15-Pad4)") (class "Default")
      (node (ref "SW15") (pin "4") (pinfunction "4_4") (pintype "passive"))
    )
    (net (code "58") (name "unconnected-(SW16-Pad3)") (class "Default")
      (node (ref "SW16") (pin "3") (pinfunction "3_3") (pintype "passive"))
    )
    (net (code "59") (name "unconnected-(SW17-Pad4)") (class "Default")
      (node (ref "SW17") (pin "4") (pinfunction "4_4") (pintype "passive"))
    )
    (net (code "60") (name "unconnected-(SW18-Pad4)") (class "Default")
      (node (ref "SW18") (pin "4") (pinfunction "4_4") (pintype "passive"))
    )
    (net (code "61") (name "unconnected-(U7-DIODE-Pad5)") (class "Default")
      (node (ref "U7") (pin "5") (pinfunction "DIODE_5") (pintype "passive"))
    )
    (net (code "62") (name "unconnected-(U7-DIODE-Pad6)") (class "Default")
      (node (ref "U7") (pin "6") (pinfunction "DIODE_6") (pintype "passive"))
    )
  )
)
